# main.net
KiCad netlist of a schematic drawn in Altium Designer
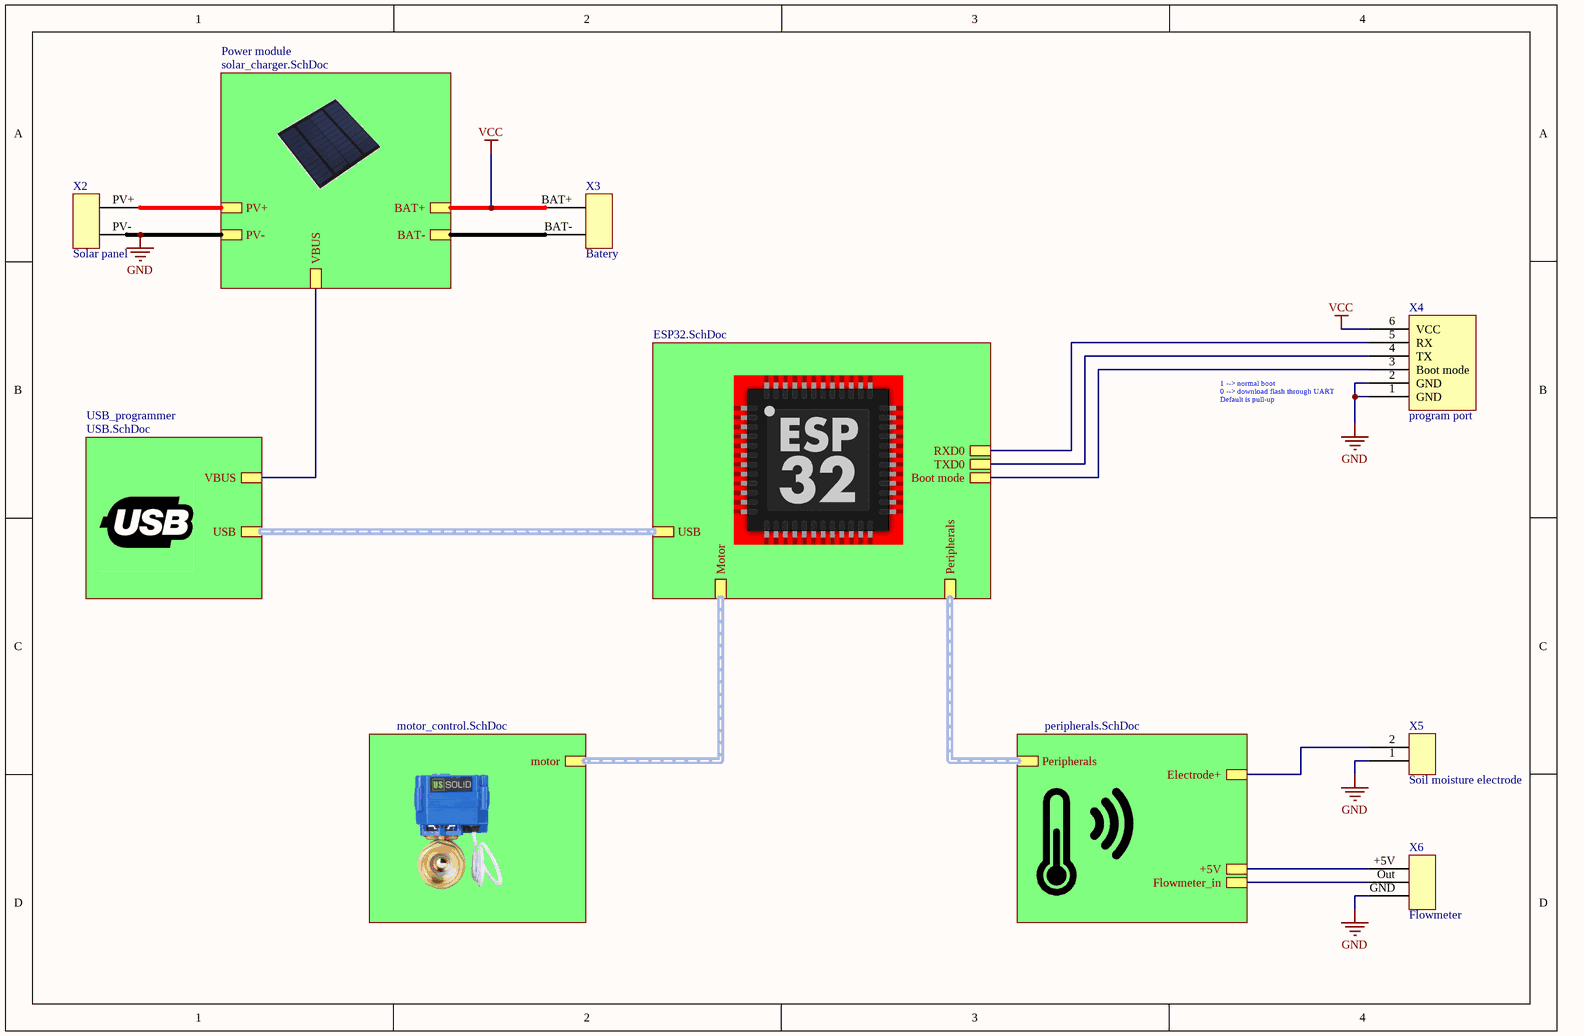
[diagram p0: main.SchDoc]

(export (version "E")
  (design (tool "Eeschema 10.0.6"))
  (components
    (comp (ref "X2")
      (value "Solar panel")
      (footprint "Solar Panel connenctor")
      (libsource (lib "WateringSystem_lib") (part "Solar panel"))
    )
    (comp (ref "X3")
      (value "Batery")
      (footprint "Battery connector")
      (libsource (lib "WateringSystem_lib") (part "Batery"))
    )
    (comp (ref "X4")
      (value "program port")
      (footprint "A2543WV-6P")
      (fields (field (name "LCSC PART #") "C239366"))
      (libsource (lib "WateringSystem_lib") (part "program port - 6 pin"))
    )
    (comp (ref "X5")
      (value "Soil moisture electrode")
      (footprint "Soil moisture sensor - long")
      (libsource (lib "WateringSystem_lib") (part "Soil moisture sensor"))
    )
    (comp (ref "X6")
      (value "Flowmeter")
      (footprint "Flowmeter")
      (libsource (lib "WateringSystem_lib") (part "Flowmeter"))
    )
  )
  (nets
    (net (code "1") (name "/+5V") (class "Default")
      (node (ref "X6") (pin "+5V") (pinfunction "3_+5V") (pintype "passive"))
    )
    (net (code "2") (name "/BAT-") (class "Default")
      (node (ref "X3") (pin "BAT-") (pinfunction "1_BAT-") (pintype "passive"))
    )
    (net (code "3") (name "/Boot mode") (class "Default")
      (node (ref "X4") (pin "3") (pinfunction "Boot_mode_3") (pintype "passive"))
    )
    (net (code "4") (name "/Electrode+") (class "Default")
      (node (ref "X5") (pin "2") (pinfunction "2_2") (pintype "passive"))
    )
    (net (code "5") (name "/Flowmeter_in") (class "Default")
      (node (ref "X6") (pin "Out") (pinfunction "2_Out") (pintype "passive"))
    )
    (net (code "7") (name "/PV+") (class "Default")
      (node (ref "X2") (pin "PV+") (pinfunction "2_PV+") (pintype "passive"))
    )
    (net (code "9") (name "/RXD0") (class "Default")
      (node (ref "X4") (pin "5") (pinfunction "RX_5") (pintype "passive"))
    )
    (net (code "10") (name "/TXD0") (class "Default")
      (node (ref "X4") (pin "4") (pinfunction "TX_4") (pintype "passive"))
    )
    (net (code "13") (name "GND") (class "Default")
      (node (ref "X2") (pin "PV-") (pinfunction "1_PV-") (pintype "passive"))
      (node (ref "X4") (pin "1") (pinfunction "GND_1") (pintype "passive"))
      (node (ref "X4") (pin "2") (pinfunction "GND_2") (pintype "passive"))
      (node (ref "X5") (pin "1") (pinfunction "1_1") (pintype "passive"))
      (node (ref "X6") (pin "GND") (pinfunction "1_GND") (pintype "passive"))
    )
    (net (code "14") (name "VCC") (class "Default")
      (node (ref "X3") (pin "BAT+") (pinfunction "2_BAT+") (pintype "passive"))
      (node (ref "X4") (pin "6") (pinfunction "VCC_6") (pintype "passive"))
    )
  )
)
